# Buck-Bost_2.net
KiCad netlist of a schematic drawn in Altium Designer
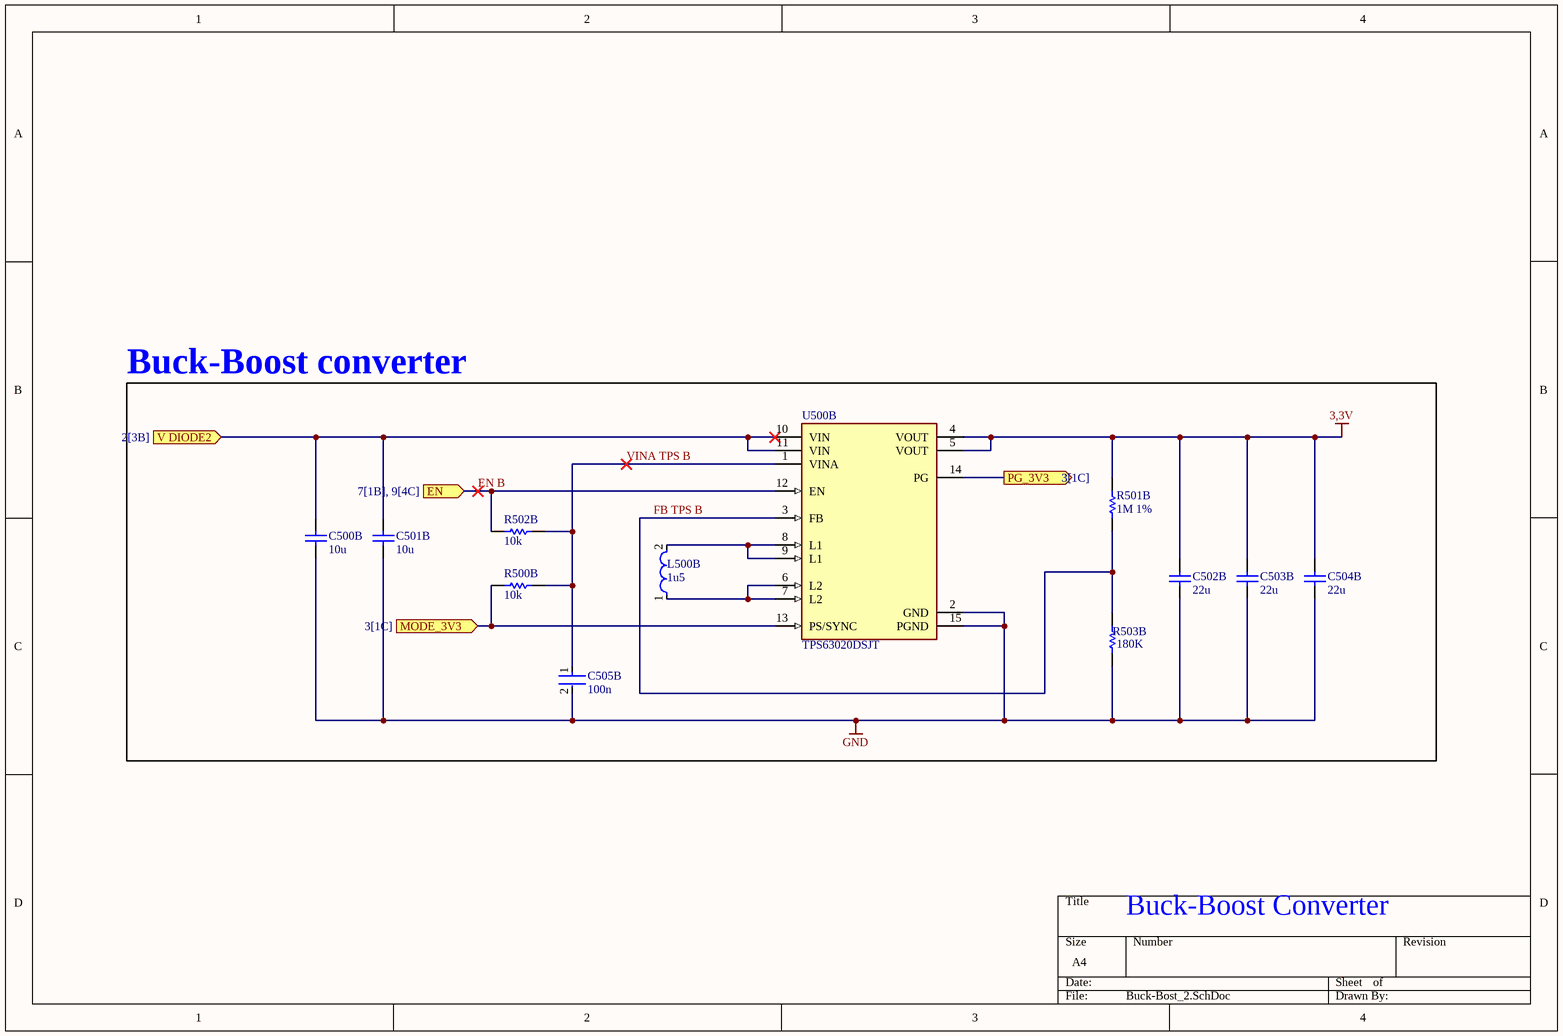
[diagram p0: Buck-Bost_2.SchDoc]

(export (version "E")
  (design (tool "Eeschema 10.0.6"))
  (components
    (comp (ref "C500B")
      (value "10u")
      (footprint "CAPC3216X180X50LL20T25")
      (description "Chip Capacitor, 10 uF, +/- 10%, 10 V, -55 to 125 degC, 1206 (3216 Metric), RoHS, Tape and Reel")
      (fields (field (name "TOLERANCE") "10%") (field (name "MANUFACTURER") "Kemet"))
      (libsource (lib "Altium Content Vault") (part "CAP-NP-2"))
    )
    (comp (ref "C501B")
      (value "10u")
      (footprint "CAPC3216X180X50LL20T25")
      (description "Chip Capacitor, 10 uF, +/- 10%, 10 V, -55 to 125 degC, 1206 (3216 Metric), RoHS, Tape and Reel")
      (fields (field (name "TOLERANCE") "10%") (field (name "MANUFACTURER") "Kemet"))
      (libsource (lib "Altium Content Vault") (part "CAP-NP-2"))
    )
    (comp (ref "C502B")
      (value "22u")
      (footprint "CAPC1206(3216)190_L")
      (description "CAP 22uF 6.3V ±20% 1206 (3216 Metric) Thickness 1.9mm SMD")
      (fields (field (name "TOLERANCE") "Â±20%"))
      (libsource (lib "Altium Content Vault") (part "CAP"))
    )
    (comp (ref "C503B")
      (value "22u")
      (footprint "CAPC1206(3216)190_L")
      (description "CAP 22uF 6.3V ±20% 1206 (3216 Metric) Thickness 1.9mm SMD")
      (fields (field (name "TOLERANCE") "Â±20%"))
      (libsource (lib "Altium Content Vault") (part "CAP"))
    )
    (comp (ref "C504B")
      (value "22u")
      (footprint "CAPC1206(3216)190_L")
      (description "CAP 22uF 6.3V ±20% 1206 (3216 Metric) Thickness 1.9mm SMD")
      (fields (field (name "TOLERANCE") "Â±20%"))
      (libsource (lib "Altium Content Vault") (part "CAP"))
    )
    (comp (ref "C505B")
      (value "100n")
      (footprint "FP-CGA3E-0_3-0_1-IPC_A")
      (description "Cap Ceramic 100nF 50V X7R 10% Pad SMD 0603 +125°C Automotive T/R")
      (fields (field (name "TOLERANCE") "10%") (field (name "VOLTAGE") "50V"))
      (libsource (lib "Altium Content Vault") (part "b4654b650e69147ec39a6b967a45e02"))
    )
    (comp (ref "L500B")
      (value "1u5")
      (footprint "FP-DFE252010C-IPC_A")
      (description "Shielded Wirewound Inductor 1.5uH  2500mA 0.072Ω 1008 (2520)")
      (fields (field (name "TOLERANCE") "20%"))
      (libsource (lib "Altium Content Vault") (part "725321dda6339637d4d059423bc1c3c"))
    )
    (comp (ref "R500B")
      (value "10k")
      (footprint "RESC2013X60X35NL10T20")
      (description "Chip Resistor, 10 KOhm, +/- 1%, 0.125 W, -55 to 155 degC, 0805 (2012 Metric), RoHS, Tape and Reel")
      (fields (field (name "MANUFACTURER") "Yageo"))
      (libsource (lib "Altium Content Vault") (part "RES-2"))
    )
    (comp (ref "R501B")
      (value "1M 1%")
      (footprint "RESC1608X55X25LL10T15")
      (description "Chip Resistor, 1 MOhm, +/- 1%, 100 mW, -55 to 155 degC, 0603 (1608 Metric), RoHS, Tape and Reel")
      (fields (field (name "TOLERANCE") "20%"))
      (libsource (lib "Altium Content Vault") (part "RES-2"))
    )
    (comp (ref "R502B")
      (value "10k")
      (footprint "RESC2013X60X35NL10T20")
      (description "Chip Resistor, 10 KOhm, +/- 1%, 0.125 W, -55 to 155 degC, 0805 (2012 Metric), RoHS, Tape and Reel")
      (fields (field (name "MANUFACTURER") "Yageo"))
      (libsource (lib "Altium Content Vault") (part "RES-2"))
    )
    (comp (ref "R503B")
      (value "180K")
      (footprint "RESC1005X40X25NL05T10")
      (description "Chip Resistor, 180 KOhm, +/- 1%, 62.5 mW, -55 to 155 degC, 0402 (1005 Metric), RoHS, Tape and Reel")
      (fields (field (name "TOLERANCE") "1%") (field (name "MANUFACTURER") "Basic Passives"))
      (libsource (lib "Altium Content Vault") (part "RES-2"))
    )
    (comp (ref "U500B")
      (value "TPS63020DSJT")
      (footprint "FP-DSJ0014A-MFG")
      (description "IC REG BCK BST ADJ 3.5A 14VSON")
      (fields
        (field (name "MANUFACTURER") "Texas Instruments")
        (field (name "OCTOPART") "https://octopart.com/tps63020dsjt-texas+instruments-12976119")
      )
      (libsource (lib "Altium Content Vault") (part "ca84f4b88d1e031d86a58c77b9c066d"))
    )
  )
  (nets
    (net (code "1") (name "/EN") (class "Default")
      (node (ref "R502B") (pin "1") (pinfunction "1_1") (pintype "passive"))
      (node (ref "U500B") (pin "12") (pinfunction "EN_12") (pintype "input"))
    )
    (net (code "3") (name "/FB TPS B") (class "Default")
      (node (ref "R501B") (pin "1") (pinfunction "1_1") (pintype "passive"))
      (node (ref "R503B") (pin "2") (pinfunction "2_2") (pintype "passive"))
      (node (ref "U500B") (pin "3") (pinfunction "FB_3") (pintype "input"))
    )
    (net (code "4") (name "/MODE_3V3") (class "Default")
      (node (ref "R500B") (pin "1") (pinfunction "1_1") (pintype "passive"))
      (node (ref "U500B") (pin "13") (pinfunction "PS/SYNC_13") (pintype "input"))
    )
    (net (code "5") (name "/PG_3V3") (class "Default")
      (node (ref "U500B") (pin "14") (pinfunction "PG_14") (pintype "open_collector"))
    )
    (net (code "6") (name "/V DIODE2") (class "Default")
      (node (ref "C500B") (pin "2") (pinfunction "2_2") (pintype "passive"))
      (node (ref "C501B") (pin "2") (pinfunction "2_2") (pintype "passive"))
      (node (ref "U500B") (pin "10") (pinfunction "VIN_10") (pintype "power_in"))
      (node (ref "U500B") (pin "11") (pinfunction "VIN_11") (pintype "power_in"))
    )
    (net (code "8") (name "/VINA TPS B") (class "Default")
      (node (ref "C505B") (pin "1") (pinfunction "1_1") (pintype "passive"))
      (node (ref "R500B") (pin "2") (pinfunction "2_2") (pintype "passive"))
      (node (ref "R502B") (pin "2") (pinfunction "2_2") (pintype "passive"))
      (node (ref "U500B") (pin "1") (pinfunction "VINA_1") (pintype "power_in"))
    )
    (net (code "9") (name "3,3V") (class "Default")
      (node (ref "C502B") (pin "2") (pinfunction "2_2") (pintype "passive"))
      (node (ref "C503B") (pin "2") (pinfunction "2_2") (pintype "passive"))
      (node (ref "C504B") (pin "2") (pinfunction "2_2") (pintype "passive"))
      (node (ref "R501B") (pin "2") (pinfunction "2_2") (pintype "passive"))
      (node (ref "U500B") (pin "4") (pinfunction "VOUT_4") (pintype "power_in"))
      (node (ref "U500B") (pin "5") (pinfunction "VOUT_5") (pintype "power_in"))
    )
    (net (code "10") (name "GND") (class "Default")
      (node (ref "C500B") (pin "1") (pinfunction "1_1") (pintype "passive"))
      (node (ref "C501B") (pin "1") (pinfunction "1_1") (pintype "passive"))
      (node (ref "C502B") (pin "1") (pinfunction "1_1") (pintype "passive"))
      (node (ref "C503B") (pin "1") (pinfunction "1_1") (pintype "passive"))
      (node (ref "C504B") (pin "1") (pinfunction "1_1") (pintype "passive"))
      (node (ref "C505B") (pin "2") (pinfunction "2_2") (pintype "passive"))
      (node (ref "R503B") (pin "1") (pinfunction "1_1") (pintype "passive"))
      (node (ref "U500B") (pin "15") (pinfunction "PGND_15") (pintype "power_in"))
      (node (ref "U500B") (pin "2") (pinfunction "GND_2") (pintype "power_in"))
    )
    (net (code "11") (name "Net-(L500B-Pad1)") (class "Default")
      (node (ref "L500B") (pin "1") (pinfunction "1_1") (pintype "passive"))
      (node (ref "U500B") (pin "6") (pinfunction "L2_6") (pintype "input"))
      (node (ref "U500B") (pin "7") (pinfunction "L2_7") (pintype "input"))
    )
    (net (code "12") (name "Net-(L500B-Pad2)") (class "Default")
      (node (ref "L500B") (pin "2") (pinfunction "2_2") (pintype "passive"))
      (node (ref "U500B") (pin "8") (pinfunction "L1_8") (pintype "input"))
      (node (ref "U500B") (pin "9") (pinfunction "L1_9") (pintype "input"))
    )
  )
)
